# ESP_with_usb_2.net
KiCad netlist of a schematic drawn in Altium Designer
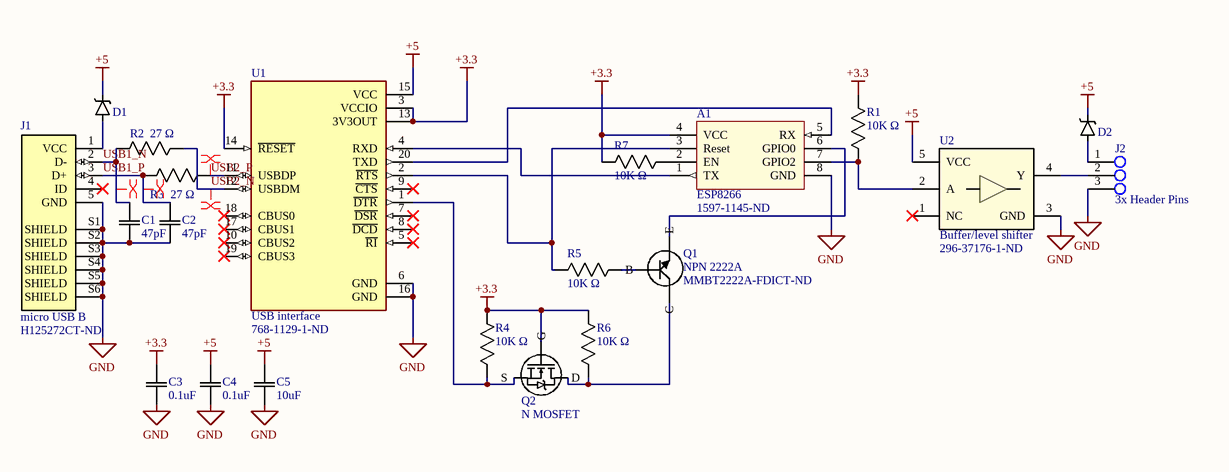
[diagram p0: ESP_with_usb_2.SchDoc]

(export (version "E")
  (design (tool "Eeschema 10.0.6"))
  (components
    (comp (ref "A1")
      (value "ESP8266")
      (footprint "ESP8266")
      (description "RX TXRX MODULE WIFI TRACE ANT TH")
      (fields (field (name "SUPPLIER PART NUMBER 1") "1597-1145-ND"))
      (libsource (lib "ESP_helper") (part "ESP8266"))
    )
    (comp (ref "C1")
      (value "47pF")
      (footprint "CC0805N")
      (description "CAP CER 47PF 50V C0G/NP0 0805")
      (fields
        (field (name "MANUFACTURER_PART_NUMBER") "CC0805KRX7R9BB104")
        (field (name "COPYRIGHT") "Copyright (C) 2018 Accelerated Designs. All rights reserved")
      )
      (libsource (lib "ESP_helper") (part "C0805C470J5GACTU"))
    )
    (comp (ref "C2")
      (value "47pF")
      (footprint "CC0805N")
      (description "CAP CER 47PF 50V C0G/NP0 0805")
      (fields
        (field (name "MANUFACTURER_PART_NUMBER") "CC0805KRX7R9BB104")
        (field (name "COPYRIGHT") "Copyright (C) 2018 Accelerated Designs. All rights reserved")
      )
      (libsource (lib "ESP_helper") (part "C0805C470J5GACTU"))
    )
    (comp (ref "C3")
      (value "0.1uF")
      (footprint "CC0805N")
      (description "CAP CER 0.1UF 50V X7R 0805")
      (fields
        (field (name "MANUFACTURER_PART_NUMBER") "CC0805KRX7R9BB104")
        (field (name "COPYRIGHT") "Copyright (C) 2018 Accelerated Designs. All rights reserved")
      )
      (libsource (lib "ESP_helper") (part "CC0805KRX7R9BB10"))
    )
    (comp (ref "C4")
      (value "0.1uF")
      (footprint "CC0805N")
      (description "CAP CER 0.1UF 50V X7R 0805")
      (fields
        (field (name "MANUFACTURER_PART_NUMBER") "CC0805KRX7R9BB104")
        (field (name "COPYRIGHT") "Copyright (C) 2018 Accelerated Designs. All rights reserved")
      )
      (libsource (lib "ESP_helper") (part "CC0805KRX7R9BB10"))
    )
    (comp (ref "C5")
      (value "10uF")
      (footprint "CC0805N")
      (description "CAP CER 10UF 6.3V X5R 0805")
      (fields
        (field (name "MANUFACTURER_PART_NUMBER") "CC0805KRX7R9BB104")
        (field (name "COPYRIGHT") "Copyright (C) 2018 Accelerated Designs. All rights reserved")
      )
      (libsource (lib "ESP_helper") (part "C0805C106K9PACTU"))
    )
    (comp (ref "D1")
      (value "Diode, Schottky")
      (footprint "SOD-323")
      (description "DIODE SCHOTTKY 23V 1A SOD323")
      (fields (field (name "MP") "BAT20JFILM") (field (name "MF") "STMicroelectronics"))
      (libsource (lib "ESP_helper") (part "BAT20JFILM"))
    )
    (comp (ref "D2")
      (value "Diode, Schottky")
      (footprint "SOD-323")
      (description "DIODE SCHOTTKY 23V 1A SOD323")
      (fields (field (name "MP") "BAT20JFILM") (field (name "MF") "STMicroelectronics"))
      (libsource (lib "ESP_helper") (part "BAT20JFILM"))
    )
    (comp (ref "J1")
      (value "micro USB B")
      (footprint "Micro USB B (rev 2)")
      (description "CONN RCPT USB2.0 MICRO B SMD R/A")
      (fields
        (field (name "MANUFACTURER_PART_NUMBER") "ZX62D-B-5P8(30)")
        (field (name "SUPPLIER PART NUMBER 1") "H125272CT-ND")
        (field (name "COPYRIGHT") "Copyright (C) 2018 Accelerated Designs. All rights reserved")
      )
      (libsource (lib "ESP_helper") (part "ZX62D-B-5P8(30)"))
    )
    (comp (ref "J2")
      (value "3x Header Pins")
      (footprint "3 HEADER PIN")
      (description "CONN HEADER VERT 5POS 2.54MM")
      (fields
        (field (name "MANUFACTURER_PART_NUMBER") "77311-818-36LF")
        (field (name "COPYRIGHT") "Copyright (C) 2018 Accelerated Designs. All rights reserved")
      )
      (libsource (lib "ESP_helper") (part "3x Header Pin"))
    )
    (comp (ref "Q1")
      (value "NPN 2222A")
      (footprint "ESP_helper:SOT-23-3")
      (description "TRANS NPN 40V 0.6A SMD SOT23-3")
      (fields
        (field (name "MF") "Diodes Inc.")
        (field (name "MP") "MMBT2222A-7-F")
        (field (name "SUPPLIER PART NUMBER 1") "MMBT2222A-FDICT-ND")
      )
      (libsource (lib "ESP_helper") (part "MMBT2222A-7-F"))
    )
    (comp (ref "Q2")
      (value "N MOSFET")
      (footprint "SOT-323")
      (description "MOSFET N-CH 60V 0.31A SOT323")
      (fields
        (field (name "MANUFACTURER_PART_NUMBER") "2N7002,215")
        (field (name "COPYRIGHT") "Copyright (C) 2018 Accelerated Designs. All rights reserved")
      )
      (libsource (lib "ESP_helper") (part "2N7002PW,115"))
    )
    (comp (ref "R1")
      (value "10K Ω")
      (footprint "CC0805N")
      (description "RES SMD 10K OHM 1% 1/8W 0805")
      (fields
        (field (name "MANUFACTURER_PART_NUMBER") "RC0805FR-0710KL")
        (field (name "COPYRIGHT") "Copyright (C) 2018 Accelerated Designs. All rights reserved")
      )
      (libsource (lib "ESP_helper") (part "RC0805FR-0710KL"))
    )
    (comp (ref "R2")
      (value "27 Ω")
      (footprint "CC0805N")
      (description "RES 27 OHM 1% 1/4W 0805")
      (fields
        (field (name "MANUFACTURER_PART_NUMBER") "RC0805FR-0710KL")
        (field (name "COPYRIGHT") "Copyright (C) 2018 Accelerated Designs. All rights reserved")
      )
      (libsource (lib "ESP_helper") (part "RK73H2ATTD27R0F"))
    )
    (comp (ref "R3")
      (value "27 Ω")
      (footprint "CC0805N")
      (description "RES 27 OHM 1% 1/4W 0805")
      (fields
        (field (name "MANUFACTURER_PART_NUMBER") "RC0805FR-0710KL")
        (field (name "COPYRIGHT") "Copyright (C) 2018 Accelerated Designs. All rights reserved")
      )
      (libsource (lib "ESP_helper") (part "RK73H2ATTD27R0F"))
    )
    (comp (ref "R4")
      (value "10K Ω")
      (footprint "CC0805N")
      (description "RES SMD 10K OHM 1% 1/8W 0805")
      (fields
        (field (name "MANUFACTURER_PART_NUMBER") "RC0805FR-0710KL")
        (field (name "COPYRIGHT") "Copyright (C) 2018 Accelerated Designs. All rights reserved")
      )
      (libsource (lib "ESP_helper") (part "RC0805FR-0710KL"))
    )
    (comp (ref "R5")
      (value "10K Ω")
      (footprint "CC0805N")
      (description "RES SMD 10K OHM 1% 1/8W 0805")
      (fields
        (field (name "MANUFACTURER_PART_NUMBER") "RC0805FR-0710KL")
        (field (name "COPYRIGHT") "Copyright (C) 2018 Accelerated Designs. All rights reserved")
      )
      (libsource (lib "ESP_helper") (part "RC0805FR-0710KL"))
    )
    (comp (ref "R6")
      (value "10K Ω")
      (footprint "CC0805N")
      (description "RES SMD 10K OHM 1% 1/8W 0805")
      (fields
        (field (name "MANUFACTURER_PART_NUMBER") "RC0805FR-0710KL")
        (field (name "COPYRIGHT") "Copyright (C) 2018 Accelerated Designs. All rights reserved")
      )
      (libsource (lib "ESP_helper") (part "RC0805FR-0710KL"))
    )
    (comp (ref "R7")
      (value "10K Ω")
      (footprint "CC0805N")
      (description "RES SMD 10K OHM 1% 1/8W 0805")
      (fields
        (field (name "MANUFACTURER_PART_NUMBER") "RC0805FR-0710KL")
        (field (name "COPYRIGHT") "Copyright (C) 2018 Accelerated Designs. All rights reserved")
      )
      (libsource (lib "ESP_helper") (part "RC0805FR-0710KL"))
    )
    (comp (ref "U1")
      (value "USB interface")
      (footprint "ESP_helper:20-SSOP")
      (description "USB Bridge, USB to UART USB 2.0 UART Interface 20-SSOP")
      (fields
        (field (name "MP") "FT231XS-R")
        (field (name "MF") "FTDI,")
        (field (name "SUPPLIER PART NUMBER 1") "768-1129-1-ND")
      )
      (libsource (lib "ESP_helper") (part "FT231XS-R"))
    )
    (comp (ref "U2")
      (value "Buffer/level shifter")
      (footprint "SOT-23-5")
      (description "IC BUF NON-INVERT 5.5V SOT23-5")
      (fields
        (field (name "PARTNUMBER") "SN74LV1T34DBV")
        (field (name "MANUFACTURER") "Texas Instruments")
        (field (name "SUPPLIER PART NUMBER 1") "296-37176-1-ND")
        (field (name "COPYRIGHT") "Copyright (C) 2018 Accelerated Designs. All rights reserved")
      )
      (libsource (lib "ESP_helper") (part "SN74LV1T34DBVR"))
    )
  )
  (nets
    (net (code "1") (name "+3.3") (class "Default")
      (node (ref "A1") (pin "4") (pinfunction "VCC_4") (pintype "power_in"))
      (node (ref "C3") (pin "2") (pinfunction "2_2") (pintype "passive"))
      (node (ref "Q2") (pin "1") (pinfunction "G_1") (pintype "passive"))
      (node (ref "R1") (pin "1") (pinfunction "1_1") (pintype "passive"))
      (node (ref "R4") (pin "1") (pinfunction "1_1") (pintype "passive"))
      (node (ref "R6") (pin "1") (pinfunction "1_1") (pintype "passive"))
      (node (ref "R7") (pin "1") (pinfunction "1_1") (pintype "passive"))
      (node (ref "U1") (pin "13") (pinfunction "3V3OUT_13") (pintype "power_in"))
      (node (ref "U1") (pin "14") (pinfunction "~{RESET}_14") (pintype "input"))
      (node (ref "U1") (pin "3") (pinfunction "VCCIO_3") (pintype "power_in"))
    )
    (net (code "2") (name "+5") (class "Default")
      (node (ref "C4") (pin "2") (pinfunction "2_2") (pintype "passive"))
      (node (ref "C5") (pin "2") (pinfunction "2_2") (pintype "passive"))
      (node (ref "D1") (pin "C") (pinfunction "C_C") (pintype "passive"))
      (node (ref "D2") (pin "C") (pinfunction "C_C") (pintype "passive"))
      (node (ref "U1") (pin "15") (pinfunction "VCC_15") (pintype "power_in"))
      (node (ref "U2") (pin "5") (pinfunction "VCC_5") (pintype "power_in"))
    )
    (net (code "3") (name "/USB1_N") (class "Default")
      (node (ref "C1") (pin "2") (pinfunction "2_2") (pintype "passive"))
      (node (ref "J1") (pin "2") (pinfunction "D-_2") (pintype "bidirectional"))
      (node (ref "R2") (pin "2") (pinfunction "2_2") (pintype "passive"))
    )
    (net (code "4") (name "/USB1_P") (class "Default")
      (node (ref "C2") (pin "2") (pinfunction "2_2") (pintype "passive"))
      (node (ref "J1") (pin "3") (pinfunction "D+_3") (pintype "bidirectional"))
      (node (ref "R3") (pin "2") (pinfunction "2_2") (pintype "passive"))
    )
    (net (code "5") (name "/USB2_N") (class "Default")
      (node (ref "R2") (pin "1") (pinfunction "1_1") (pintype "passive"))
      (node (ref "U1") (pin "12") (pinfunction "USBDM_12") (pintype "bidirectional"))
    )
    (net (code "6") (name "/USB2_P") (class "Default")
      (node (ref "R3") (pin "1") (pinfunction "1_1") (pintype "passive"))
      (node (ref "U1") (pin "11") (pinfunction "USBDP_11") (pintype "bidirectional"))
    )
    (net (code "7") (name "GND") (class "Default")
      (node (ref "A1") (pin "8") (pinfunction "GND_8") (pintype "power_in"))
      (node (ref "C1") (pin "1") (pinfunction "1_1") (pintype "passive"))
      (node (ref "C2") (pin "1") (pinfunction "1_1") (pintype "passive"))
      (node (ref "C3") (pin "1") (pinfunction "1_1") (pintype "passive"))
      (node (ref "C4") (pin "1") (pinfunction "1_1") (pintype "passive"))
      (node (ref "C5") (pin "1") (pinfunction "1_1") (pintype "passive"))
      (node (ref "J1") (pin "5") (pinfunction "GND_5") (pintype "power_in"))
      (node (ref "J1") (pin "S1") (pinfunction "SHIELD_S1") (pintype "passive"))
      (node (ref "J1") (pin "S2") (pinfunction "SHIELD_S2") (pintype "passive"))
      (node (ref "J1") (pin "S3") (pinfunction "SHIELD_S3") (pintype "passive"))
      (node (ref "J1") (pin "S4") (pinfunction "SHIELD_S4") (pintype "passive"))
      (node (ref "J1") (pin "S5") (pinfunction "SHIELD_S5") (pintype "passive"))
      (node (ref "J1") (pin "S6") (pinfunction "SHIELD_S6") (pintype "passive"))
      (node (ref "J2") (pin "3") (pinfunction "3_3") (pintype "passive"))
      (node (ref "U1") (pin "16") (pinfunction "GND_16") (pintype "power_in"))
      (node (ref "U1") (pin "6") (pinfunction "GND_6") (pintype "power_in"))
      (node (ref "U2") (pin "3") (pinfunction "GND_3") (pintype "power_in"))
    )
    (net (code "8") (name "Net-(A1-EN)") (class "Default")
      (node (ref "A1") (pin "2") (pinfunction "EN_2") (pintype "passive"))
      (node (ref "R7") (pin "2") (pinfunction "2_2") (pintype "passive"))
    )
    (net (code "9") (name "Net-(A1-GPIO0)") (class "Default")
      (node (ref "A1") (pin "6") (pinfunction "GPIO0_6") (pintype "passive"))
      (node (ref "Q1") (pin "2") (pinfunction "E_2") (pintype "passive"))
    )
    (net (code "10") (name "Net-(A1-GPIO2)") (class "Default")
      (node (ref "A1") (pin "7") (pinfunction "GPIO2_7") (pintype "passive"))
      (node (ref "R1") (pin "2") (pinfunction "2_2") (pintype "passive"))
      (node (ref "U2") (pin "2") (pinfunction "A_2") (pintype "passive"))
    )
    (net (code "11") (name "Net-(A1-RX)") (class "Default")
      (node (ref "A1") (pin "5") (pinfunction "RX_5") (pintype "input"))
      (node (ref "U1") (pin "20") (pinfunction "TXD_20") (pintype "output"))
    )
    (net (code "12") (name "Net-(A1-Reset)") (class "Default")
      (node (ref "A1") (pin "3") (pinfunction "Reset_3") (pintype "passive"))
      (node (ref "R5") (pin "2") (pinfunction "2_2") (pintype "passive"))
      (node (ref "U1") (pin "2") (pinfunction "~{RTS}_2") (pintype "output"))
    )
    (net (code "13") (name "Net-(A1-TX)") (class "Default")
      (node (ref "A1") (pin "1") (pinfunction "TX_1") (pintype "output"))
      (node (ref "U1") (pin "4") (pinfunction "RXD_4") (pintype "input"))
    )
    (net (code "14") (name "Net-(D2-PadA)") (class "Default")
      (node (ref "D2") (pin "A") (pinfunction "A_A") (pintype "passive"))
      (node (ref "J2") (pin "1") (pinfunction "1_1") (pintype "passive"))
    )
    (net (code "15") (name "Net-(J1-VCC)") (class "Default")
      (node (ref "D1") (pin "A") (pinfunction "A_A") (pintype "passive"))
      (node (ref "J1") (pin "1") (pinfunction "VCC_1") (pintype "power_in"))
    )
    (net (code "16") (name "Net-(Q1-B)") (class "Default")
      (node (ref "Q1") (pin "1") (pinfunction "B_1") (pintype "passive"))
      (node (ref "R5") (pin "1") (pinfunction "1_1") (pintype "passive"))
    )
    (net (code "17") (name "Net-(Q1-C)") (class "Default")
      (node (ref "Q1") (pin "3") (pinfunction "C_3") (pintype "passive"))
      (node (ref "Q2") (pin "3") (pinfunction "D_3") (pintype "passive"))
      (node (ref "R6") (pin "2") (pinfunction "2_2") (pintype "passive"))
    )
    (net (code "18") (name "Net-(Q2-S)") (class "Default")
      (node (ref "Q2") (pin "2") (pinfunction "S_2") (pintype "passive"))
      (node (ref "R4") (pin "2") (pinfunction "2_2") (pintype "passive"))
      (node (ref "U1") (pin "1") (pinfunction "~{DTR}_1") (pintype "output"))
    )
    (net (code "19") (name "Net-(U2-Y)") (class "Default")
      (node (ref "J2") (pin "2") (pinfunction "2_2") (pintype "passive"))
      (node (ref "U2") (pin "4") (pinfunction "Y_4") (pintype "passive"))
    )
    (net (code "20") (name "unconnected-(J1-ID-Pad4)") (class "Default")
      (node (ref "J1") (pin "4") (pinfunction "ID_4") (pintype "passive+no_connect"))
    )
    (net (code "21") (name "unconnected-(U1-CBUS0-Pad18)") (class "Default")
      (node (ref "U1") (pin "18") (pinfunction "CBUS0_18") (pintype "bidirectional+no_connect"))
    )
    (net (code "22") (name "unconnected-(U1-CBUS1-Pad17)") (class "Default")
      (node (ref "U1") (pin "17") (pinfunction "CBUS1_17") (pintype "bidirectional+no_connect"))
    )
    (net (code "23") (name "unconnected-(U1-CBUS2-Pad10)") (class "Default")
      (node (ref "U1") (pin "10") (pinfunction "CBUS2_10") (pintype "bidirectional+no_connect"))
    )
    (net (code "24") (name "unconnected-(U1-CBUS3-Pad19)") (class "Default")
      (node (ref "U1") (pin "19") (pinfunction "CBUS3_19") (pintype "bidirectional+no_connect"))
    )
    (net (code "25") (name "unconnected-(U1-~{CTS}-Pad9)") (class "Default")
      (node (ref "U1") (pin "9") (pinfunction "~{CTS}_9") (pintype "input+no_connect"))
    )
    (net (code "26") (name "unconnected-(U1-~{DCD}-Pad8)") (class "Default")
      (node (ref "U1") (pin "8") (pinfunction "~{DCD}_8") (pintype "input+no_connect"))
    )
    (net (code "27") (name "unconnected-(U1-~{DSR}-Pad7)") (class "Default")
      (node (ref "U1") (pin "7") (pinfunction "~{DSR}_7") (pintype "input+no_connect"))
    )
    (net (code "28") (name "unconnected-(U1-~{RI}-Pad5)") (class "Default")
      (node (ref "U1") (pin "5") (pinfunction "~{RI}_5") (pintype "input+no_connect"))
    )
    (net (code "29") (name "unconnected-(U2-NC-Pad1)") (class "Default")
      (node (ref "U2") (pin "1") (pinfunction "NC_1") (pintype "passive+no_connect"))
    )
  )
)
